# DSO_Trig.net
KiCad netlist of a schematic drawn in Altium Designer
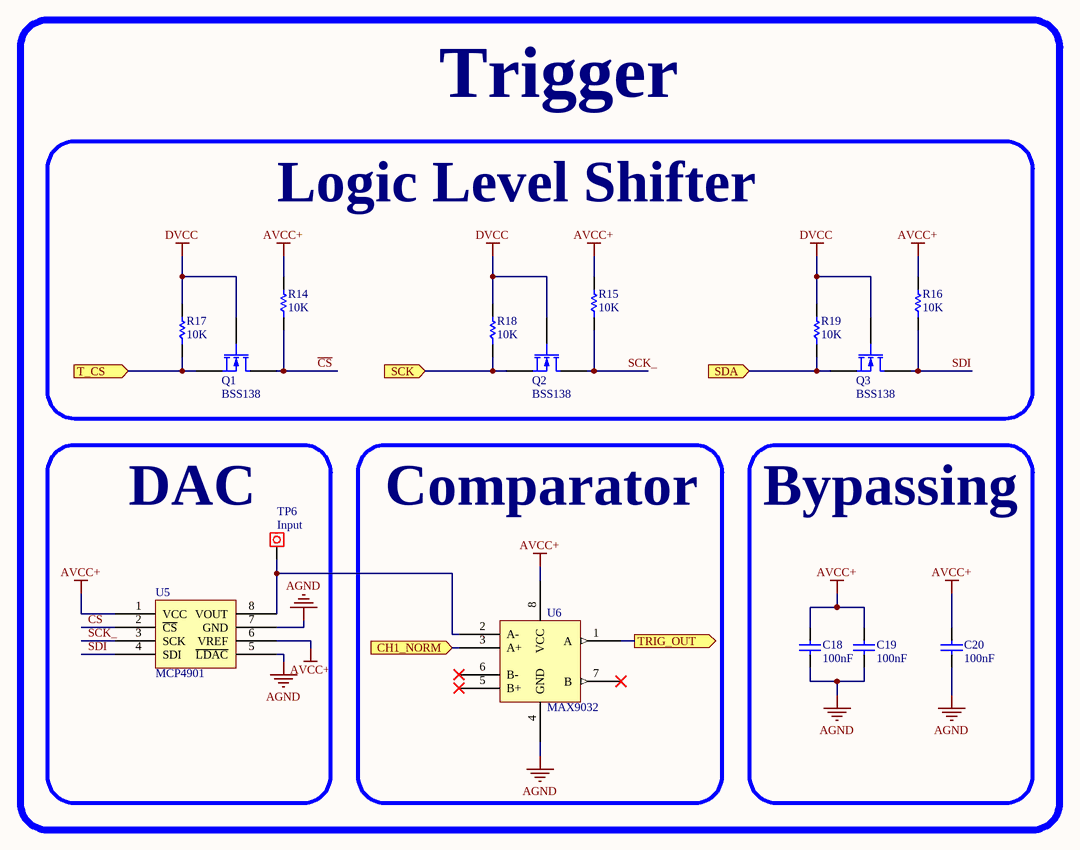
[diagram p0: DSO_Trig.SchDoc]

(export (version "E")
  (design (tool "Eeschema 10.0.6"))
  (components
    (comp (ref "C18")
      (value "100nF")
      (footprint "0805C")
      (description "Capacitor")
      (fields (field (name "REVIEWED BY") "RM - 2018/08/05"))
      (libsource (lib "DSO") (part "C"))
    )
    (comp (ref "C19")
      (value "100nF")
      (footprint "0805C")
      (description "Capacitor")
      (fields (field (name "REVIEWED BY") "RM - 2018/08/05"))
      (libsource (lib "DSO") (part "C"))
    )
    (comp (ref "C20")
      (value "100nF")
      (footprint "0805C")
      (description "Capacitor")
      (fields (field (name "REVIEWED BY") "RM - 2018/08/05"))
      (libsource (lib "DSO") (part "C"))
    )
    (comp (ref "Q1")
      (value "BSS138")
      (footprint "SOT23")
      (description "N-Channel MOSFET")
      (fields (field (name "PUBLISHER") "Altium Limited"))
      (libsource (lib "DSO") (part "MOSFET-N"))
    )
    (comp (ref "Q2")
      (value "BSS138")
      (footprint "SOT23")
      (description "N-Channel MOSFET")
      (fields (field (name "PUBLISHER") "Altium Limited"))
      (libsource (lib "DSO") (part "MOSFET-N"))
    )
    (comp (ref "Q3")
      (value "BSS138")
      (footprint "SOT23")
      (description "N-Channel MOSFET")
      (fields (field (name "PUBLISHER") "Altium Limited"))
      (libsource (lib "DSO") (part "MOSFET-N"))
    )
    (comp (ref "R14")
      (value "10K")
      (footprint "0805")
      (description "Resistor")
      (fields (field (name "REVIEWED BY") "RM - 2018/08/05"))
      (libsource (lib "DSO") (part "R"))
    )
    (comp (ref "R15")
      (value "10K")
      (footprint "0805")
      (description "Resistor")
      (fields (field (name "REVIEWED BY") "RM - 2018/08/05"))
      (libsource (lib "DSO") (part "R"))
    )
    (comp (ref "R16")
      (value "10K")
      (footprint "0805")
      (description "Resistor")
      (fields (field (name "REVIEWED BY") "RM - 2018/08/05"))
      (libsource (lib "DSO") (part "R"))
    )
    (comp (ref "R17")
      (value "10K")
      (footprint "0805")
      (description "Resistor")
      (fields (field (name "REVIEWED BY") "RM - 2018/08/05"))
      (libsource (lib "DSO") (part "R"))
    )
    (comp (ref "R18")
      (value "10K")
      (footprint "0805")
      (description "Resistor")
      (fields (field (name "REVIEWED BY") "RM - 2018/08/05"))
      (libsource (lib "DSO") (part "R"))
    )
    (comp (ref "R19")
      (value "10K")
      (footprint "0805")
      (description "Resistor")
      (fields (field (name "REVIEWED BY") "RM - 2018/08/05"))
      (libsource (lib "DSO") (part "R"))
    )
    (comp (ref "TP6")
      (value "Input")
      (footprint "Testpoin")
      (description "Pad")
      (fields (field (name "Comment") "INPUT"))
      (libsource (lib "DSO") (part "Test Point"))
    )
    (comp (ref "U5")
      (value "MCP4901")
      (footprint "SOIC-8")
      (description "DAC 8bit SPI")
      (fields (field (name "REVIEWED BY") "RM - 2018/08/05"))
      (libsource (lib "DSO") (part "MCP4901"))
    )
    (comp (ref "U6")
      (value "MAX9032")
      (footprint "SOIC-8")
      (description "Dual Comparator")
      (fields (field (name "REVIEWED BY") "RM - 2018/08/05"))
      (libsource (lib "DSO") (part "MAX9032"))
    )
  )
  (nets
    (net (code "1") (name "/CH1_NORM") (class "Default")
      (node (ref "U6") (pin "3") (pinfunction "A+_3") (pintype "passive"))
    )
    (net (code "2") (name "/SCK") (class "Default")
      (node (ref "Q2") (pin "2") (pinfunction "2_2") (pintype "passive"))
      (node (ref "R18") (pin "1") (pintype "passive"))
    )
    (net (code "3") (name "/SCK_") (class "Default")
      (node (ref "Q2") (pin "3") (pinfunction "3_3") (pintype "passive"))
      (node (ref "R15") (pin "1") (pintype "passive"))
      (node (ref "U5") (pin "3") (pinfunction "SCK_3") (pintype "passive"))
    )
    (net (code "4") (name "/SDA") (class "Default")
      (node (ref "Q3") (pin "2") (pinfunction "2_2") (pintype "passive"))
      (node (ref "R19") (pin "1") (pintype "passive"))
    )
    (net (code "5") (name "/SDI") (class "Default")
      (node (ref "Q3") (pin "3") (pinfunction "3_3") (pintype "passive"))
      (node (ref "R16") (pin "1") (pintype "passive"))
      (node (ref "U5") (pin "4") (pinfunction "SDI_4") (pintype "passive"))
    )
    (net (code "6") (name "/TRIG_OUT") (class "Default")
      (node (ref "U6") (pin "1") (pinfunction "A_1") (pintype "output"))
    )
    (net (code "7") (name "/T_CS") (class "Default")
      (node (ref "Q1") (pin "2") (pinfunction "2_2") (pintype "passive"))
      (node (ref "R17") (pin "1") (pintype "passive"))
    )
    (net (code "8") (name "/~{CS}") (class "Default")
      (node (ref "Q1") (pin "3") (pinfunction "3_3") (pintype "passive"))
      (node (ref "R14") (pin "1") (pintype "passive"))
      (node (ref "U5") (pin "2") (pinfunction "~{CS}_2") (pintype "passive"))
    )
    (net (code "9") (name "AGND") (class "Default")
      (node (ref "C18") (pin "1") (pinfunction "1_1") (pintype "passive"))
      (node (ref "C19") (pin "1") (pinfunction "1_1") (pintype "passive"))
      (node (ref "C20") (pin "1") (pinfunction "1_1") (pintype "passive"))
      (node (ref "U5") (pin "5") (pinfunction "~{LDAC}_5") (pintype "passive"))
      (node (ref "U5") (pin "7") (pinfunction "GND_7") (pintype "passive"))
      (node (ref "U6") (pin "4") (pinfunction "GND_4") (pintype "passive"))
    )
    (net (code "10") (name "AVCC+") (class "Default")
      (node (ref "C18") (pin "2") (pinfunction "2_2") (pintype "passive"))
      (node (ref "C19") (pin "2") (pinfunction "2_2") (pintype "passive"))
      (node (ref "C20") (pin "2") (pinfunction "2_2") (pintype "passive"))
      (node (ref "R14") (pin "2") (pintype "passive"))
      (node (ref "R15") (pin "2") (pintype "passive"))
      (node (ref "R16") (pin "2") (pintype "passive"))
      (node (ref "U5") (pin "1") (pinfunction "VCC_1") (pintype "passive"))
      (node (ref "U5") (pin "6") (pinfunction "VREF_6") (pintype "passive"))
      (node (ref "U6") (pin "8") (pinfunction "VCC_8") (pintype "passive"))
    )
    (net (code "11") (name "DVCC") (class "Default")
      (node (ref "Q1") (pin "1") (pinfunction "1_1") (pintype "passive"))
      (node (ref "Q2") (pin "1") (pinfunction "1_1") (pintype "passive"))
      (node (ref "Q3") (pin "1") (pinfunction "1_1") (pintype "passive"))
      (node (ref "R17") (pin "2") (pintype "passive"))
      (node (ref "R18") (pin "2") (pintype "passive"))
      (node (ref "R19") (pin "2") (pintype "passive"))
    )
    (net (code "12") (name "Net-(U5-VOUT)") (class "Default")
      (node (ref "TP6") (pin "1") (pintype "passive"))
      (node (ref "U5") (pin "8") (pinfunction "VOUT_8") (pintype "passive"))
      (node (ref "U6") (pin "2") (pinfunction "A-_2") (pintype "passive"))
    )
    (net (code "13") (name "unconnected-(U6-B+-Pad5)") (class "Default")
      (node (ref "U6") (pin "5") (pinfunction "B+_5") (pintype "passive+no_connect"))
    )
    (net (code "14") (name "unconnected-(U6-B--Pad6)") (class "Default")
      (node (ref "U6") (pin "6") (pinfunction "B-_6") (pintype "passive+no_connect"))
    )
    (net (code "15") (name "unconnected-(U6-B-Pad7)") (class "Default")
      (node (ref "U6") (pin "7") (pinfunction "B_7") (pintype "output+no_connect"))
    )
  )
)
